# fan_control.net
KiCad netlist of a schematic drawn in EAGLE
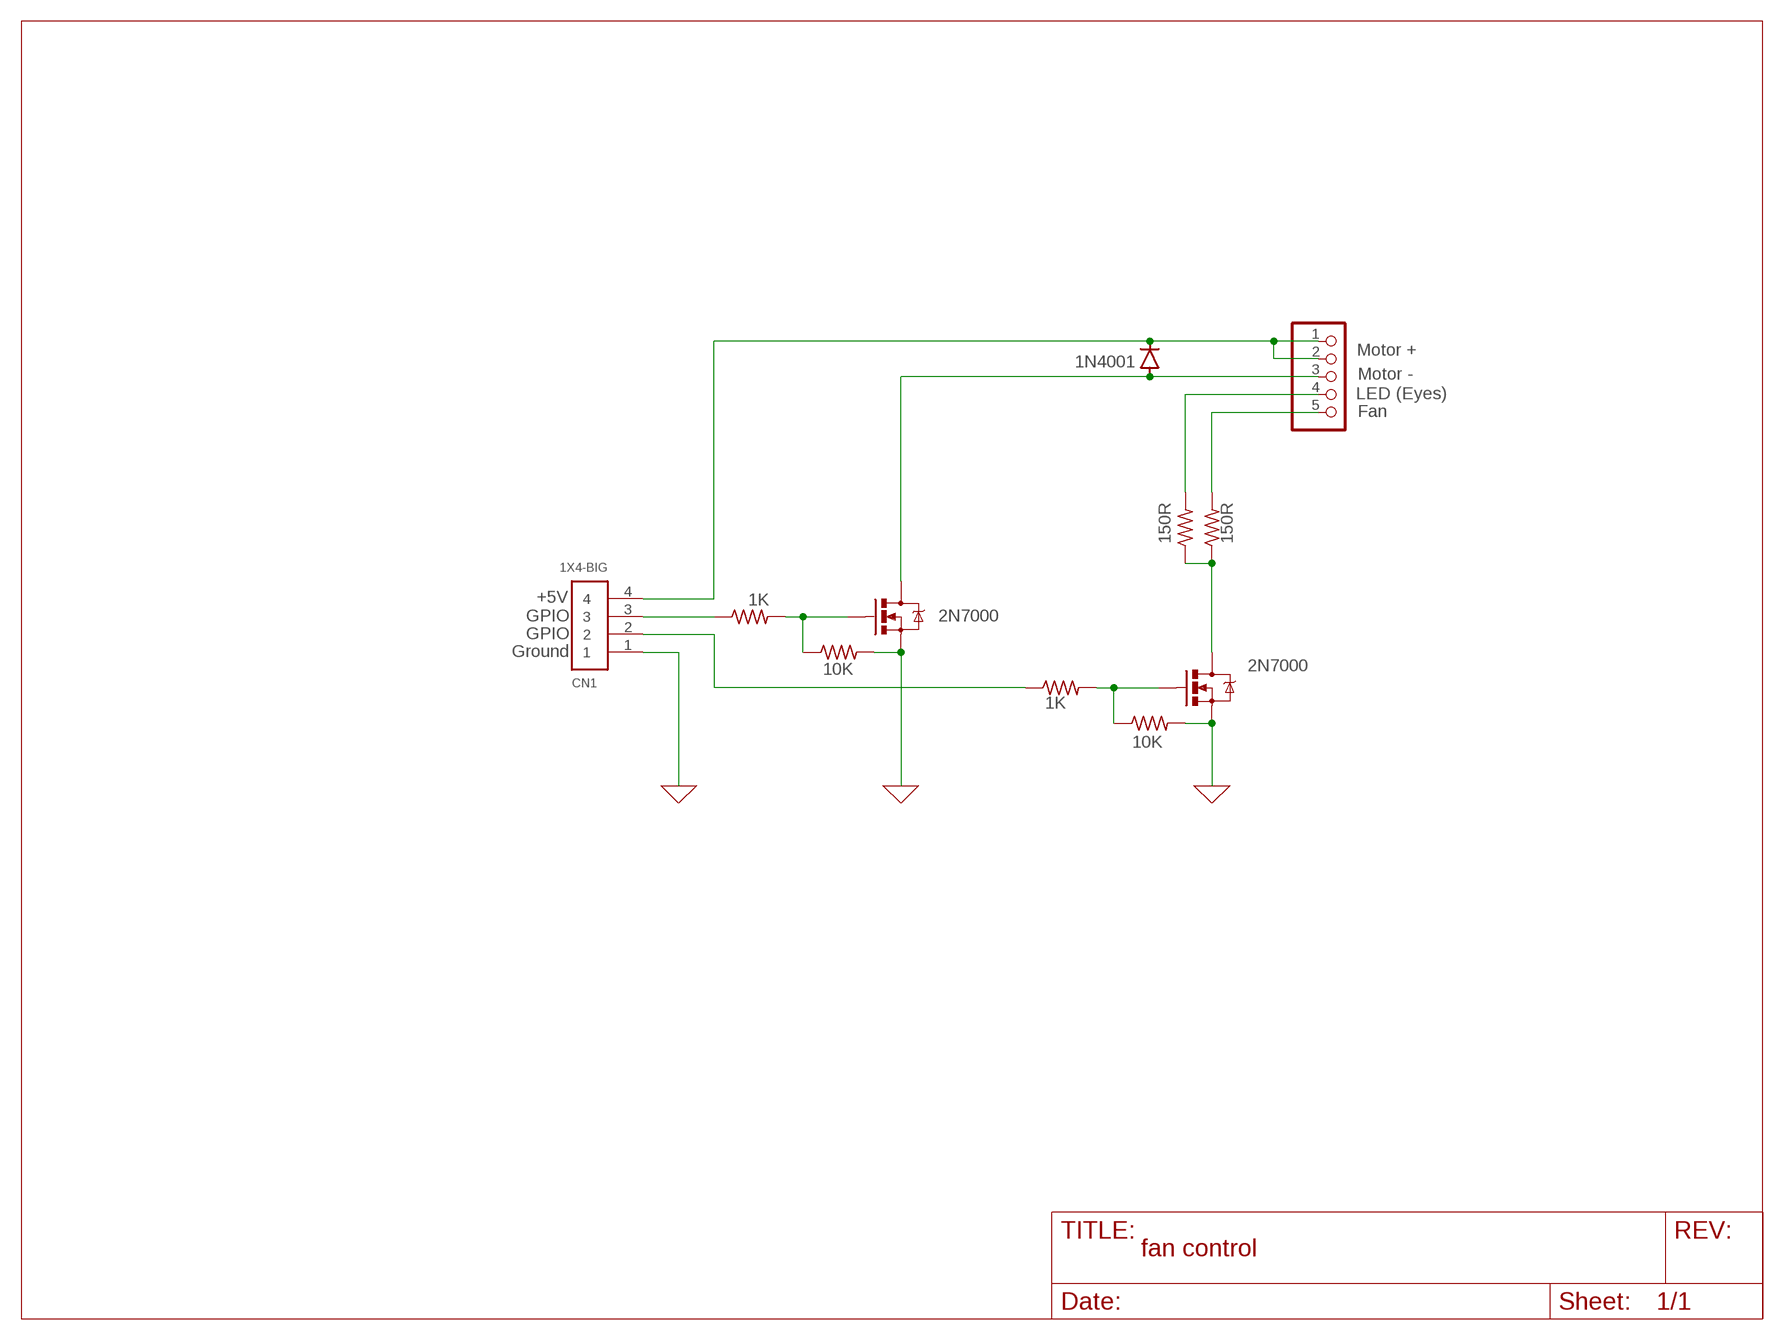
[diagram p0: schematic, sheet 1]

(export (version "E")
  (design (tool "Eeschema 10.0.6"))
  (components
    (comp (ref "CN1")
      (value "1X4-BIG")
      (footprint "eagle-import:1X04-BIG")
      (libsource (lib "eagle-import") (part "1X4-BIG"))
    )
    (comp (ref "D1")
      (value "1N4001")
      (footprint "eagle-import:DO-41")
      (fields
        (field (name "DIGIKEY_PART_NUMBER") "1N4004MSCT-ND")
        (field (name "MANUFACTURER") "Micro Commercial Co")
        (field (name "MPN") "1N4004")
        (field (name "CREATED_BY") "PCBLayout.com")
      )
      (libsource (lib "eagle-import") (part "1N4004"))
    )
    (comp (ref "JP1")
      (value "PINHD-1X5")
      (footprint "eagle-import:1X05")
      (libsource (lib "eagle-import") (part "PINHD-1X5"))
    )
    (comp (ref "Q1")
      (value "MOSFET-NCHANNEL2N7000")
      (footprint "eagle-import:TO-92")
      (libsource (lib "eagle-import") (part "MOSFET-NCHANNEL2N7000"))
    )
    (comp (ref "Q2")
      (value "MOSFET-NCHANNEL2N7000")
      (footprint "eagle-import:TO-92")
      (libsource (lib "eagle-import") (part "MOSFET-NCHANNEL2N7000"))
    )
    (comp (ref "R1")
      (value "1K")
      (footprint "eagle-import:0207_10")
      (libsource (lib "eagle-import") (part "R-US_0207/10"))
    )
    (comp (ref "R2")
      (value "10K")
      (footprint "eagle-import:0207_10")
      (libsource (lib "eagle-import") (part "R-US_0207/10"))
    )
    (comp (ref "R3")
      (value "1K")
      (footprint "eagle-import:0207_10")
      (libsource (lib "eagle-import") (part "R-US_0207/10"))
    )
    (comp (ref "R4")
      (value "10K")
      (footprint "eagle-import:0207_10")
      (libsource (lib "eagle-import") (part "R-US_0207/10"))
    )
    (comp (ref "R5")
      (value "150R")
      (footprint "eagle-import:0207_10")
      (libsource (lib "eagle-import") (part "R-US_0207/10"))
    )
    (comp (ref "R6")
      (value "150R")
      (footprint "eagle-import:0207_10")
      (libsource (lib "eagle-import") (part "R-US_0207/10"))
    )
  )
  (nets
    (net (code "1") (name "GND") (class "Default")
      (node (ref "CN1") (pin "1") (pinfunction "1_1") (pintype "bidirectional"))
      (node (ref "Q1") (pin "1") (pinfunction "S_1") (pintype "passive"))
      (node (ref "Q2") (pin "1") (pinfunction "S_1") (pintype "passive"))
      (node (ref "R2") (pin "2") (pinfunction "2_2") (pintype "passive"))
      (node (ref "R4") (pin "2") (pinfunction "2_2") (pintype "passive"))
    )
    (net (code "2") (name "Net-(CN1-Pad2)") (class "Default")
      (node (ref "CN1") (pin "2") (pinfunction "2_2") (pintype "bidirectional"))
      (node (ref "R3") (pin "1") (pinfunction "1_1") (pintype "passive"))
    )
    (net (code "3") (name "Net-(CN1-Pad3)") (class "Default")
      (node (ref "CN1") (pin "3") (pinfunction "3_3") (pintype "bidirectional"))
      (node (ref "R1") (pin "1") (pinfunction "1_1") (pintype "passive"))
    )
    (net (code "4") (name "Net-(CN1-Pad4)") (class "Default")
      (node (ref "CN1") (pin "4") (pinfunction "4_4") (pintype "bidirectional"))
      (node (ref "D1") (pin "C") (pinfunction "C_C") (pintype "passive"))
      (node (ref "JP1") (pin "1") (pinfunction "1_1") (pintype "passive"))
      (node (ref "JP1") (pin "2") (pinfunction "2_2") (pintype "passive"))
    )
    (net (code "5") (name "Net-(JP1-Pad4)") (class "Default")
      (node (ref "JP1") (pin "4") (pinfunction "4_4") (pintype "passive"))
      (node (ref "R5") (pin "2") (pinfunction "2_2") (pintype "passive"))
    )
    (net (code "6") (name "Net-(JP1-Pad5)") (class "Default")
      (node (ref "JP1") (pin "5") (pinfunction "5_5") (pintype "passive"))
      (node (ref "R6") (pin "2") (pinfunction "2_2") (pintype "passive"))
    )
    (net (code "7") (name "Net-(Q1-D)") (class "Default")
      (node (ref "D1") (pin "A") (pinfunction "A_A") (pintype "passive"))
      (node (ref "JP1") (pin "3") (pinfunction "3_3") (pintype "passive"))
      (node (ref "Q1") (pin "3") (pinfunction "D_3") (pintype "passive"))
    )
    (net (code "8") (name "Net-(Q1-G)") (class "Default")
      (node (ref "Q1") (pin "2") (pinfunction "G_2") (pintype "passive"))
      (node (ref "R1") (pin "2") (pinfunction "2_2") (pintype "passive"))
      (node (ref "R2") (pin "1") (pinfunction "1_1") (pintype "passive"))
    )
    (net (code "9") (name "Net-(Q2-D)") (class "Default")
      (node (ref "Q2") (pin "3") (pinfunction "D_3") (pintype "passive"))
      (node (ref "R5") (pin "1") (pinfunction "1_1") (pintype "passive"))
      (node (ref "R6") (pin "1") (pinfunction "1_1") (pintype "passive"))
    )
    (net (code "10") (name "Net-(Q2-G)") (class "Default")
      (node (ref "Q2") (pin "2") (pinfunction "G_2") (pintype "passive"))
      (node (ref "R3") (pin "2") (pinfunction "2_2") (pintype "passive"))
      (node (ref "R4") (pin "1") (pinfunction "1_1") (pintype "passive"))
    )
  )
)
